# Sheet2.net
KiCad netlist of a schematic drawn in Altium Designer
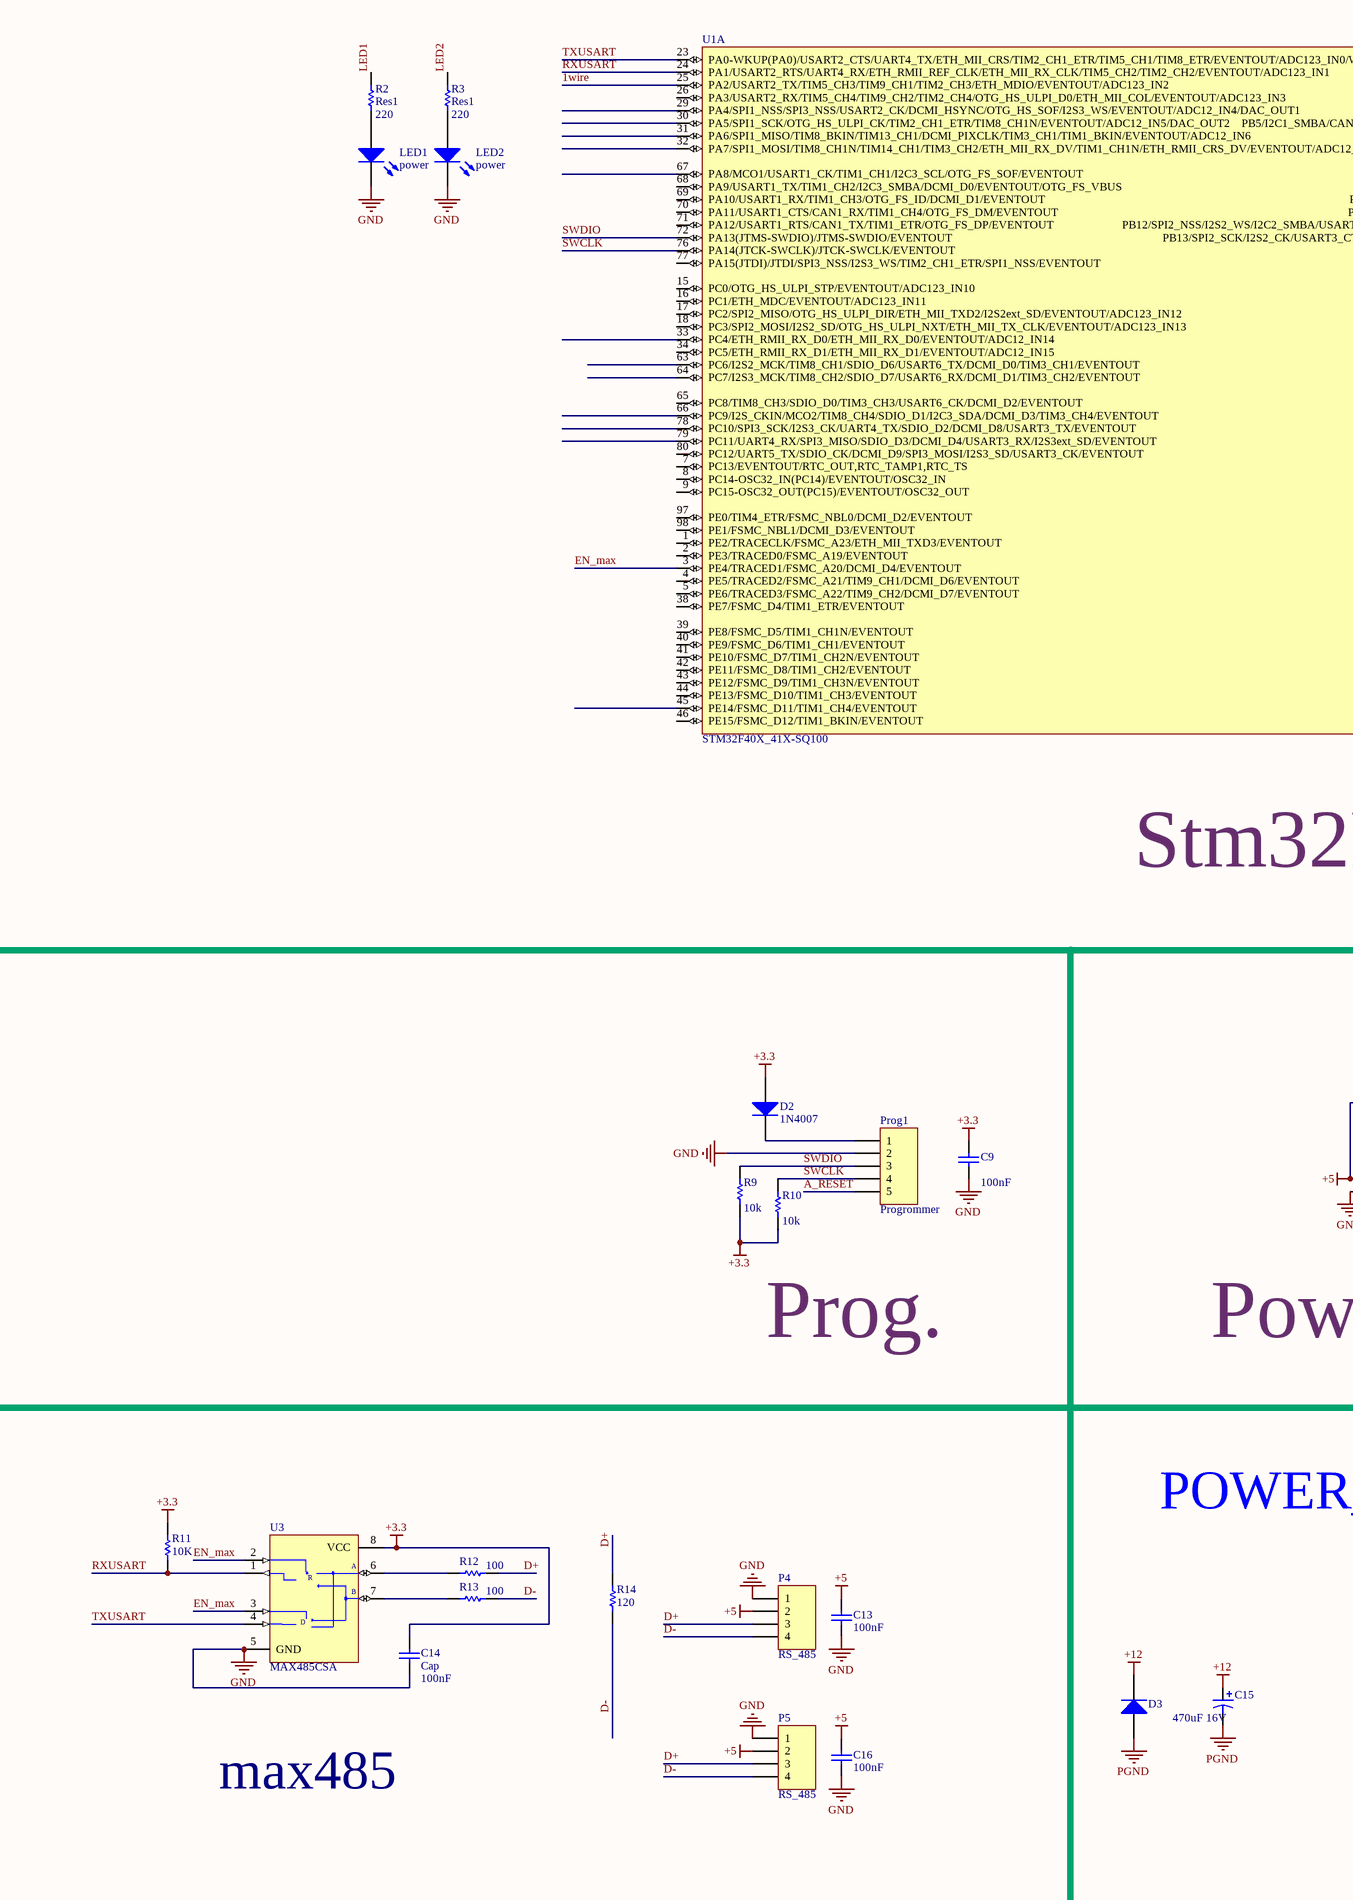
[diagram p0: Sheet2.SchDoc, left]
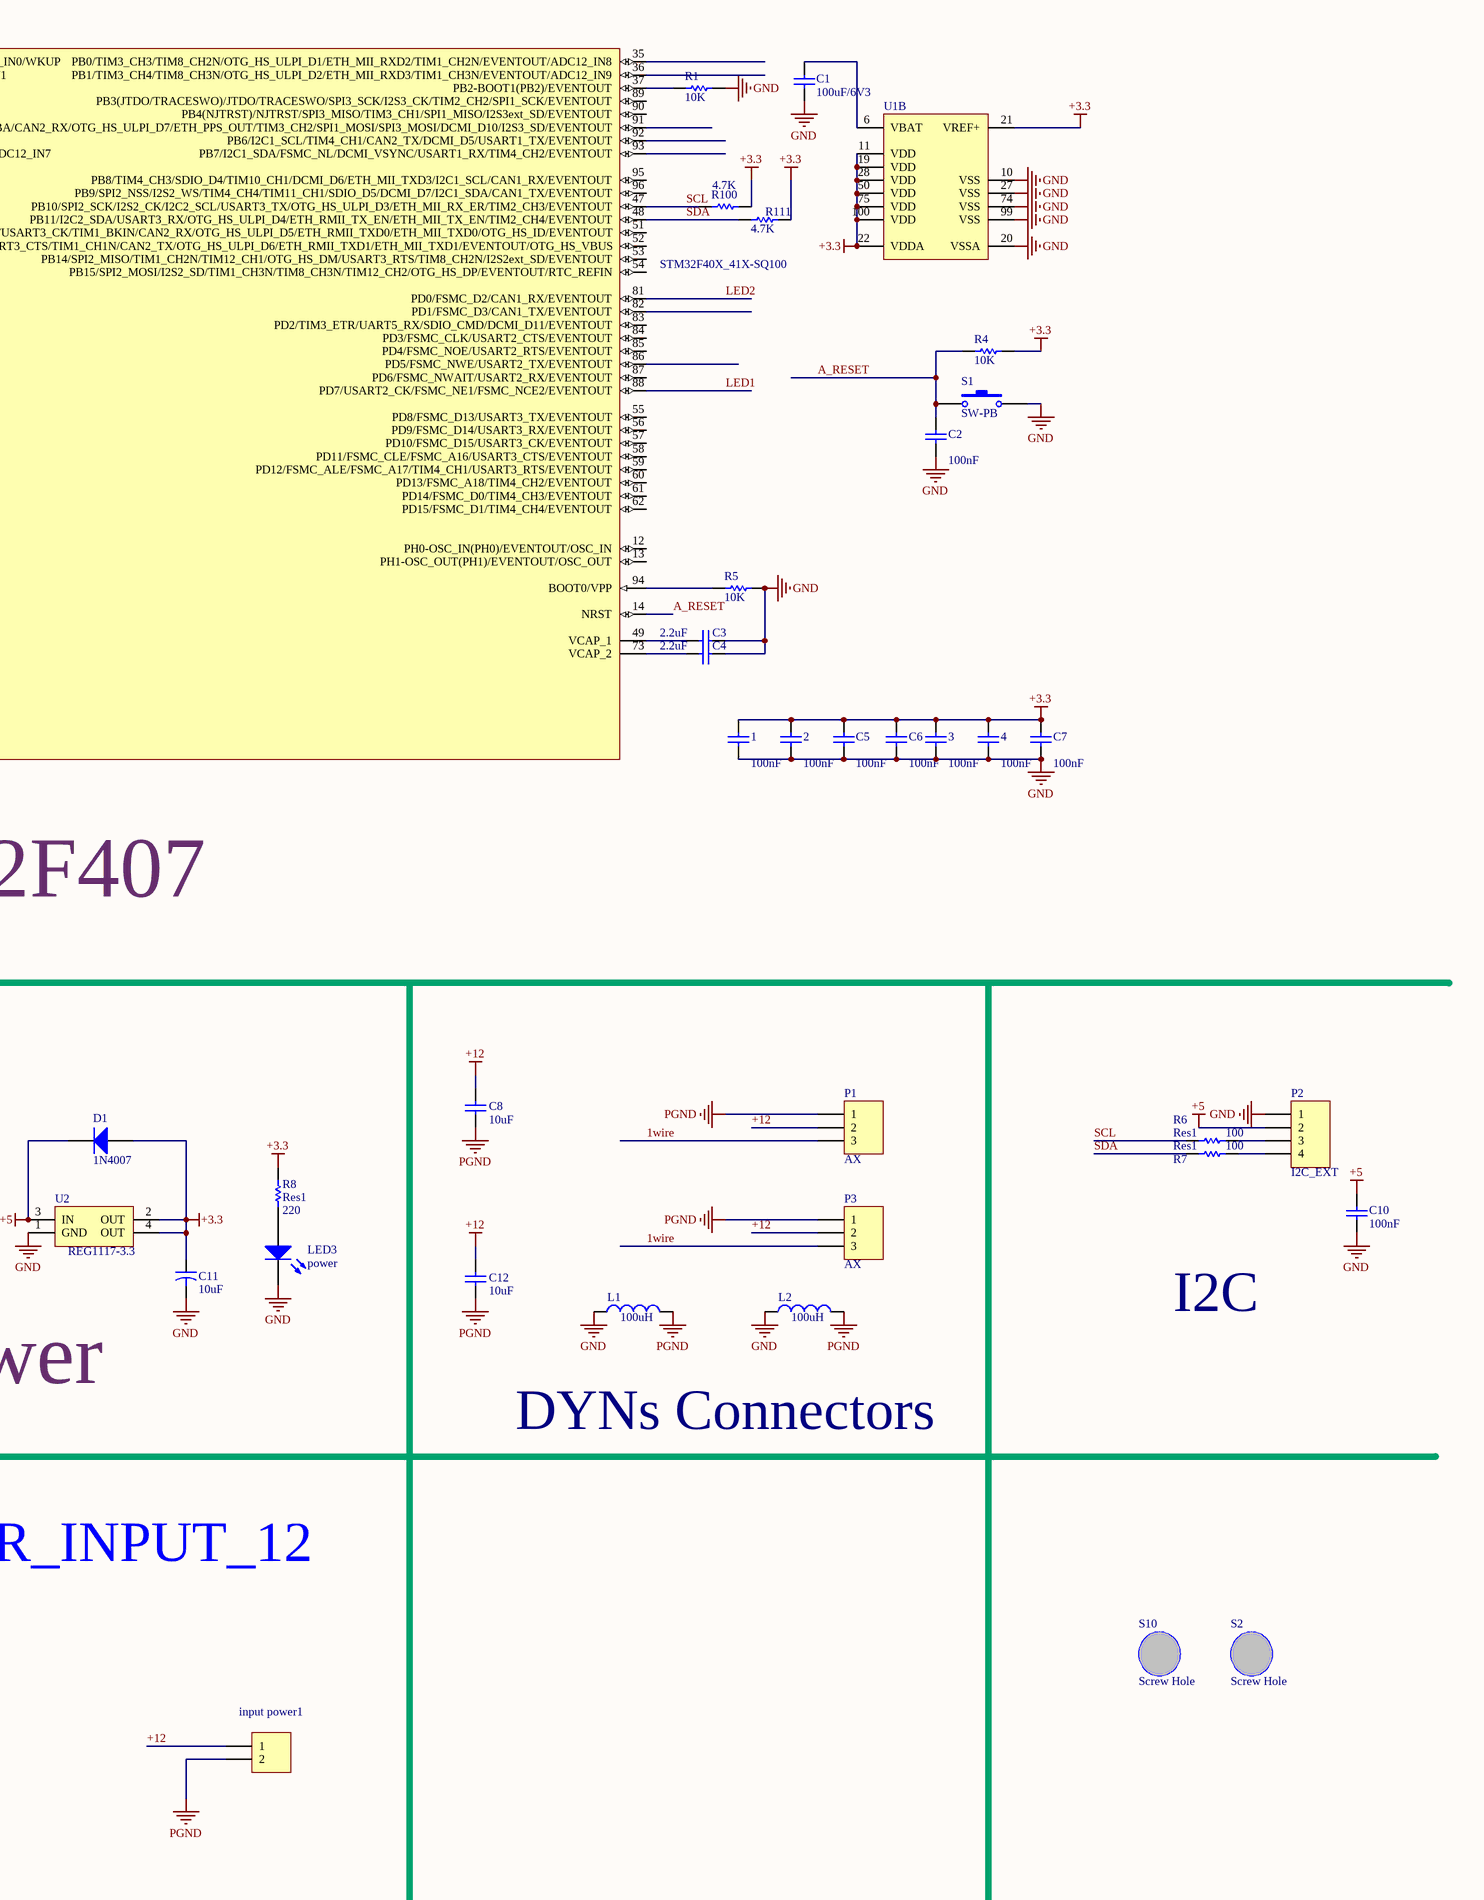
[diagram p1: Sheet2.SchDoc, right]

(export (version "E")
  (design (tool "Eeschema 10.0.6"))
  (components
    (comp (ref "1")
      (value "100nF")
      (footprint "1608[0603]")
      (description "Capacitor")
      (fields
        (field (name "MANUFACTURER") "Generic Components")
        (field (name "PUBLISHER") "Altium Hobart Technology Centre")
      )
      (libsource (lib "Miscellaneous Devices") (part "Cap"))
    )
    (comp (ref "2")
      (value "100nF")
      (footprint "1608[0603]")
      (description "Capacitor")
      (fields
        (field (name "MANUFACTURER") "Generic Components")
        (field (name "PUBLISHER") "Altium Hobart Technology Centre")
      )
      (libsource (lib "Miscellaneous Devices") (part "Cap"))
    )
    (comp (ref "3")
      (value "100nF")
      (footprint "1608[0603]")
      (description "Capacitor")
      (fields
        (field (name "MANUFACTURER") "Generic Components")
        (field (name "PUBLISHER") "Altium Hobart Technology Centre")
      )
      (libsource (lib "Miscellaneous Devices") (part "Cap"))
    )
    (comp (ref "4")
      (value "100nF")
      (footprint "1608[0603]")
      (description "Capacitor")
      (fields
        (field (name "MANUFACTURER") "Generic Components")
        (field (name "PUBLISHER") "Altium Hobart Technology Centre")
      )
      (libsource (lib "Miscellaneous Devices") (part "Cap"))
    )
    (comp (ref "C1")
      (value "100uF/6V3")
      (footprint "j1-0603")
      (description "Capacitor")
      (fields (field (name "PUBLISHER") "Altium Limited"))
      (libsource (lib "Miscellaneous Devices") (part "Cap"))
    )
    (comp (ref "C2")
      (value "100nF")
      (footprint "1608[0603]")
      (description "Capacitor")
      (fields
        (field (name "MANUFACTURER") "Generic Components")
        (field (name "PUBLISHER") "Altium Hobart Technology Centre")
      )
      (libsource (lib "Miscellaneous Devices") (part "Cap"))
    )
    (comp (ref "C3")
      (value "2.2uF")
      (footprint "j1-0603")
      (description "Capacitor")
      (fields (field (name "PUBLISHER") "Altium Limited"))
      (libsource (lib "KN2CLib") (part "Cap_UP"))
    )
    (comp (ref "C4")
      (value "2.2uF")
      (footprint "j1-0603")
      (description "Capacitor")
      (fields (field (name "PUBLISHER") "Altium Limited"))
      (libsource (lib "KN2CLib") (part "Cap_UP"))
    )
    (comp (ref "C5")
      (value "100nF")
      (footprint "1608[0603]")
      (description "Capacitor")
      (fields
        (field (name "MANUFACTURER") "Generic Components")
        (field (name "PUBLISHER") "Altium Hobart Technology Centre")
      )
      (libsource (lib "Miscellaneous Devices") (part "Cap"))
    )
    (comp (ref "C6")
      (value "100nF")
      (footprint "1608[0603]")
      (description "Capacitor")
      (fields
        (field (name "MANUFACTURER") "Generic Components")
        (field (name "PUBLISHER") "Altium Hobart Technology Centre")
      )
      (libsource (lib "Miscellaneous Devices") (part "Cap"))
    )
    (comp (ref "C7")
      (value "100nF")
      (footprint "1608[0603]")
      (description "Capacitor")
      (fields
        (field (name "MANUFACTURER") "Generic Components")
        (field (name "PUBLISHER") "Altium Hobart Technology Centre")
      )
      (libsource (lib "Miscellaneous Devices") (part "Cap"))
    )
    (comp (ref "C8")
      (value "10uF")
      (footprint "2012[0805]")
      (description "Capacitor")
      (fields (field (name "Comment") "Cap") (field (name "PUBLISHER") "Altium Limited"))
      (libsource (lib "Miscellaneous Devices") (part "Cap"))
    )
    (comp (ref "C9")
      (value "100nF")
      (footprint "1608[0603]")
      (description "Capacitor")
      (fields
        (field (name "MANUFACTURER") "Generic Components")
        (field (name "PUBLISHER") "Altium Hobart Technology Centre")
      )
      (libsource (lib "Miscellaneous Devices") (part "Cap"))
    )
    (comp (ref "C10")
      (value "100nF")
      (footprint "J1-0603")
      (description "Capacitor")
      (fields (field (name "PUBLISHER") "Altium Limited"))
      (libsource (lib "Miscellaneous Devices") (part "Cap"))
    )
    (comp (ref "C11")
      (value "10uF")
      (footprint "0805")
      (description "Capacitor")
      (fields (field (name "Comment") "Cap_El") (field (name "PUBLISHER") "Altium Limited"))
      (libsource (lib "KN2CLib") (part "Cap_El"))
    )
    (comp (ref "C12")
      (value "10uF")
      (footprint "2012[0805]")
      (description "Capacitor")
      (fields (field (name "Comment") "Cap") (field (name "PUBLISHER") "Altium Limited"))
      (libsource (lib "Miscellaneous Devices") (part "Cap"))
    )
    (comp (ref "C13")
      (value "100nF")
      (footprint "J1-0603")
      (description "Capacitor")
      (fields (field (name "PUBLISHER") "Altium Limited"))
      (libsource (lib "Miscellaneous Devices") (part "Cap"))
    )
    (comp (ref "C14")
      (value "Cap")
      (footprint "j1-0603")
      (description "Capacitor")
      (fields (field (name "ALTIUM_VALUE") "100nF") (field (name "PUBLISHER") "Altium Limited"))
      (libsource (lib "Miscellaneous Devices") (part "Cap"))
    )
    (comp (ref "C15")
      (value "470uF 16V")
      (footprint "C")
      (description "Polarized Capacitor (Radial)")
      (fields (field (name "Comment") "Cap Pol1") (field (name "PUBLISHER") "Altium Limited"))
      (libsource (lib "Miscellaneous Devices") (part "Cap Pol1"))
    )
    (comp (ref "C16")
      (value "100nF")
      (footprint "J1-0603")
      (description "Capacitor")
      (fields (field (name "PUBLISHER") "Altium Limited"))
      (libsource (lib "Miscellaneous Devices") (part "Cap"))
    )
    (comp (ref "D1")
      (value "1N4007")
      (footprint "US1M")
      (description "1 Amp General Purpose Rectifier")
      (fields (field (name "PUBLISHER") "Altium Limited"))
      (libsource (lib "KN2CLib") (part "Diode"))
    )
    (comp (ref "D2")
      (value "1N4007")
      (footprint "US1M")
      (description "1 Amp General Purpose Rectifier")
      (fields (field (name "PUBLISHER") "Altium Limited"))
      (libsource (lib "KN2CLib") (part "Diode"))
    )
    (comp (ref "D3")
      (value "~")
      (footprint "us1m")
      (description "Default Diode")
      (fields
        (field (name "MANUFACTURER") "Generic Components")
        (field (name "PUBLISHER") "Altium Hobart Technology Centre")
      )
      (libsource (lib "Miscellaneous Devices") (part "Diode"))
    )
    (comp (ref "input power1")
      (value "Header 2")
      (footprint "CON2-TIWAN")
      (description "Header, 2-Pin")
      (fields (field (name "PUBLISHER") "Altium Limited"))
      (libsource (lib "KN2CLib") (part "Header 2"))
    )
    (comp (ref "L1")
      (value "100uH")
      (footprint "2012[0805]")
      (description "Inductor")
      (fields
        (field (name "MANUFACTURER") "Generic Components")
        (field (name "PUBLISHER") "Altium Hobart Technology Centre")
      )
      (libsource (lib "Miscellaneous Devices") (part "Inductor"))
    )
    (comp (ref "L2")
      (value "100uH")
      (footprint "2012[0805]")
      (description "Inductor")
      (fields
        (field (name "MANUFACTURER") "Generic Components")
        (field (name "PUBLISHER") "Altium Hobart Technology Centre")
      )
      (libsource (lib "Miscellaneous Devices") (part "Inductor"))
    )
    (comp (ref "LED1")
      (value "power")
      (footprint "3518")
      (description "Typical BLUE SiC LED")
      (fields (field (name "PUBLISHER") "Altium Limited"))
      (libsource (lib "Miscellaneous Devices") (part "LED3"))
    )
    (comp (ref "LED2")
      (value "power")
      (footprint "3518")
      (description "Typical BLUE SiC LED")
      (fields (field (name "PUBLISHER") "Altium Limited"))
      (libsource (lib "Miscellaneous Devices") (part "LED3"))
    )
    (comp (ref "LED3")
      (value "power")
      (footprint "3518")
      (description "Typical BLUE SiC LED")
      (fields (field (name "PUBLISHER") "Altium Limited"))
      (libsource (lib "Miscellaneous Devices") (part "LED3"))
    )
    (comp (ref "P1")
      (value "AX")
      (footprint "jp circular 3")
      (description "Header, 3-Pin")
      (fields (field (name "PUBLISHER") "Altium Limited"))
      (libsource (lib "KN2CLib") (part "jp circular 3"))
    )
    (comp (ref "P2")
      (value "I2C_EXT")
      (footprint "jp circular 4")
      (description "Header, 4-Pin")
      (fields (field (name "PUBLISHER") "Altium Limited"))
      (libsource (lib "KN2CLib") (part "jp circular 4"))
    )
    (comp (ref "P3")
      (value "AX")
      (footprint "jp circular 3")
      (description "Header, 3-Pin")
      (fields (field (name "PUBLISHER") "Altium Limited"))
      (libsource (lib "KN2CLib") (part "jp circular 3"))
    )
    (comp (ref "P4")
      (value "RS_485")
      (footprint "jp circular 4")
      (description "Header, 4-Pin")
      (fields (field (name "PUBLISHER") "Altium Limited"))
      (libsource (lib "Miscellaneous Connectors") (part "Header 4"))
    )
    (comp (ref "P5")
      (value "RS_485")
      (footprint "jp circular 4")
      (description "Header, 4-Pin")
      (fields (field (name "PUBLISHER") "Altium Limited"))
      (libsource (lib "Miscellaneous Connectors") (part "Header 4"))
    )
    (comp (ref "Prog1")
      (value "Progrommer")
      (footprint "HDR1x5")
      (description "Header, 5-Pin")
      (fields (field (name "PUBLISHER") "Altium Limited"))
      (libsource (lib "Miscellaneous Connectors") (part "Header 5"))
    )
    (comp (ref "R1")
      (value "10K")
      (footprint "J1-0603")
      (description "Resistor")
      (fields (field (name "PUBLISHER") "Altium Limited"))
      (libsource (lib "Miscellaneous Devices") (part "Res1"))
    )
    (comp (ref "R2")
      (value "Res1")
      (footprint "j1-0603")
      (description "Resistor")
      (fields (field (name "ALTIUM_VALUE") "220") (field (name "PUBLISHER") "Altium Limited"))
      (libsource (lib "Miscellaneous Devices") (part "Res1"))
    )
    (comp (ref "R3")
      (value "Res1")
      (footprint "j1-0603")
      (description "Resistor")
      (fields (field (name "ALTIUM_VALUE") "220") (field (name "PUBLISHER") "Altium Limited"))
      (libsource (lib "Miscellaneous Devices") (part "Res1"))
    )
    (comp (ref "R4")
      (value "10K")
      (footprint "J1-0603")
      (description "Resistor")
      (fields (field (name "PUBLISHER") "Altium Limited"))
      (libsource (lib "Miscellaneous Devices") (part "Res1"))
    )
    (comp (ref "R5")
      (value "10K")
      (footprint "J1-0603")
      (description "Resistor")
      (fields (field (name "PUBLISHER") "Altium Limited"))
      (libsource (lib "Miscellaneous Devices") (part "Res1"))
    )
    (comp (ref "R6")
      (value "Res1")
      (footprint "j1-0603")
      (description "Resistor")
      (fields (field (name "ALTIUM_VALUE") "100") (field (name "PUBLISHER") "Altium Limited"))
      (libsource (lib "Miscellaneous Devices") (part "Res1"))
    )
    (comp (ref "R7")
      (value "Res1")
      (footprint "j1-0603")
      (description "Resistor")
      (fields (field (name "ALTIUM_VALUE") "100") (field (name "PUBLISHER") "Altium Limited"))
      (libsource (lib "Miscellaneous Devices") (part "Res1"))
    )
    (comp (ref "R8")
      (value "Res1")
      (footprint "j1-0603")
      (description "Resistor")
      (fields (field (name "ALTIUM_VALUE") "220") (field (name "PUBLISHER") "Altium Limited"))
      (libsource (lib "Miscellaneous Devices") (part "Res1"))
    )
    (comp (ref "R9")
      (value "10k")
      (footprint "J1-0603")
      (description "Semiconductor Resistor")
      (fields (field (name "PUBLISHER") "Altium Limited"))
      (libsource (lib "KN2CLib") (part "Res"))
    )
    (comp (ref "R10")
      (value "10k")
      (footprint "J1-0603")
      (description "Semiconductor Resistor")
      (fields (field (name "PUBLISHER") "Altium Limited"))
      (libsource (lib "KN2CLib") (part "Res"))
    )
    (comp (ref "R11")
      (value "10K")
      (footprint "j1-0603")
      (description "Resistor")
      (fields (field (name "Comment") "Res1") (field (name "PUBLISHER") "Altium Limited"))
      (libsource (lib "Miscellaneous Devices") (part "Res1"))
    )
    (comp (ref "R12")
      (value "100")
      (footprint "j1-0603")
      (description "Resistor")
      (fields (field (name "Comment") "Res1") (field (name "PUBLISHER") "Altium Limited"))
      (libsource (lib "Miscellaneous Devices") (part "Res1"))
    )
    (comp (ref "R13")
      (value "100")
      (footprint "j1-0603")
      (description "Resistor")
      (fields (field (name "Comment") "Res1") (field (name "PUBLISHER") "Altium Limited"))
      (libsource (lib "Miscellaneous Devices") (part "Res1"))
    )
    (comp (ref "R14")
      (value "120")
      (footprint "j1-0603")
      (description "Resistor")
      (fields (field (name "Comment") "Res1") (field (name "PUBLISHER") "Altium Limited"))
      (libsource (lib "Miscellaneous Devices") (part "Res1"))
    )
    (comp (ref "R100")
      (value "4.7K")
      (footprint "J1-0603")
      (description "Resistor")
      (fields (field (name "PUBLISHER") "Altium Limited"))
      (libsource (lib "Miscellaneous Devices") (part "Res1"))
    )
    (comp (ref "R111")
      (value "4.7K")
      (footprint "J1-0603")
      (description "Resistor")
      (fields (field (name "PUBLISHER") "Altium Limited"))
      (libsource (lib "Miscellaneous Devices") (part "Res1"))
    )
    (comp (ref "S1")
      (value "SW-PB")
      (footprint "SW-PB-4P")
      (description "Switch")
      (fields (field (name "PUBLISHER") "Altium Limited"))
      (libsource (lib "Miscellaneous Devices") (part "SW-PB"))
    )
    (comp (ref "S2")
      (value "Screw Hole")
      (footprint "Screw Holw 3-6 mm")
      (libsource (lib "KN2CLib") (part "Screw Hole"))
    )
    (comp (ref "S10")
      (value "Screw Hole")
      (footprint "Screw Holw 3-6 mm")
      (libsource (lib "KN2CLib") (part "Screw Hole"))
    )
    (comp (ref "U1")
      (value "STM32F40X_41X-SQ100")
      (footprint "100A_N")
      (libsource (lib "KN2CLib") (part "STM32F40X_41X-SQ100"))
    )
    (comp (ref "U2")
      (value "REG1117-3.3")
      (footprint "SOT223")
      (description "800mA and 1A Low Dropout Positive Regulator 2.85V, 3.3V, 5V, and Adjustable")
      (fields (field (name "PUBLISHER") "Altium Limited"))
      (libsource (lib "BB Power Mgt Voltage Regulator") (part "REG1117-3.3"))
    )
    (comp (ref "U3")
      (value "MAX485CSA")
      (footprint "NSO8_N")
      (description "Low-Power, Slew-Rate-Limited RS-485/RS-422 Transceiver")
      (fields (field (name "PUBLISHER") "Altium Limited"))
      (libsource (lib "Maxim Communication Transceiver") (part "MAX485CSA"))
    )
  )
  (nets
    (net (code "1") (name "+3.3") (class "Default")
      (node (ref "1") (pin "2") (pinfunction "2_2") (pintype "passive"))
      (node (ref "2") (pin "2") (pinfunction "2_2") (pintype "passive"))
      (node (ref "3") (pin "2") (pinfunction "2_2") (pintype "passive"))
      (node (ref "4") (pin "2") (pinfunction "2_2") (pintype "passive"))
      (node (ref "C11") (pin "1") (pinfunction "1_1") (pintype "passive"))
      (node (ref "C14") (pin "2") (pinfunction "2_2") (pintype "passive"))
      (node (ref "C5") (pin "2") (pinfunction "2_2") (pintype "passive"))
      (node (ref "C6") (pin "2") (pinfunction "2_2") (pintype "passive"))
      (node (ref "C7") (pin "2") (pinfunction "2_2") (pintype "passive"))
      (node (ref "C9") (pin "2") (pinfunction "2_2") (pintype "passive"))
      (node (ref "D1") (pin "1") (pinfunction "A_1") (pintype "passive"))
      (node (ref "D2") (pin "1") (pinfunction "A_1") (pintype "passive"))
      (node (ref "R10") (pin "2") (pinfunction "2_2") (pintype "passive"))
      (node (ref "R100") (pin "1") (pinfunction "1_1") (pintype "passive"))
      (node (ref "R11") (pin "1") (pinfunction "1_1") (pintype "passive"))
      (node (ref "R111") (pin "1") (pinfunction "1_1") (pintype "passive"))
      (node (ref "R4") (pin "1") (pinfunction "1_1") (pintype "passive"))
      (node (ref "R8") (pin "1") (pinfunction "1_1") (pintype "passive"))
      (node (ref "R9") (pin "2") (pinfunction "2_2") (pintype "passive"))
      (node (ref "U1") (pin "100") (pinfunction "VDD_100") (pintype "power_in"))
      (node (ref "U1") (pin "11") (pinfunction "VDD_11") (pintype "power_in"))
      (node (ref "U1") (pin "19") (pinfunction "VDD_19") (pintype "power_in"))
      (node (ref "U1") (pin "21") (pinfunction "VREF+_21") (pintype "power_in"))
      (node (ref "U1") (pin "22") (pinfunction "VDDA_22") (pintype "power_in"))
      (node (ref "U1") (pin "28") (pinfunction "VDD_28") (pintype "power_in"))
      (node (ref "U1") (pin "50") (pinfunction "VDD_50") (pintype "power_in"))
      (node (ref "U1") (pin "75") (pinfunction "VDD_75") (pintype "power_in"))
      (node (ref "U2") (pin "2") (pinfunction "OUT_2") (pintype "power_in"))
      (node (ref "U2") (pin "4") (pinfunction "OUT_4") (pintype "power_in"))
      (node (ref "U3") (pin "8") (pinfunction "VCC_8") (pintype "power_in"))
    )
    (net (code "2") (name "+5") (class "Default")
      (node (ref "C10") (pin "2") (pinfunction "2_2") (pintype "passive"))
      (node (ref "C13") (pin "2") (pinfunction "2_2") (pintype "passive"))
      (node (ref "C16") (pin "2") (pinfunction "2_2") (pintype "passive"))
      (node (ref "D1") (pin "2") (pinfunction "K_2") (pintype "passive"))
      (node (ref "P2") (pin "2") (pinfunction "2_2") (pintype "passive"))
      (node (ref "P4") (pin "2") (pinfunction "2_2") (pintype "passive"))
      (node (ref "P5") (pin "2") (pinfunction "2_2") (pintype "passive"))
      (node (ref "U2") (pin "3") (pinfunction "IN_3") (pintype "power_in"))
    )
    (net (code "3") (name "+12") (class "Default")
      (node (ref "C12") (pin "2") (pinfunction "2_2") (pintype "passive"))
      (node (ref "C15") (pin "1") (pinfunction "1_1") (pintype "passive"))
      (node (ref "C8") (pin "2") (pinfunction "2_2") (pintype "passive"))
      (node (ref "D3") (pin "2") (pinfunction "K_2") (pintype "passive"))
      (node (ref "P1") (pin "2") (pinfunction "2_2") (pintype "passive"))
      (node (ref "P3") (pin "2") (pinfunction "2_2") (pintype "passive"))
      (node (ref "input power1") (pin "1") (pinfunction "1_1") (pintype "passive"))
    )
    (net (code "4") (name "/1wire") (class "Default")
      (node (ref "P1") (pin "3") (pinfunction "3_3") (pintype "passive"))
      (node (ref "P3") (pin "3") (pinfunction "3_3") (pintype "passive"))
      (node (ref "U1") (pin "25") (pinfunction "PA2/USART2_TX/TIM5_CH3/TIM9_CH1/TIM2_CH3/ETH_MDIO/EVENTOUT/ADC123_IN2_25") (pintype "bidirectional"))
    )
    (net (code "5") (name "/A_RESET") (class "Default")
      (node (ref "C2") (pin "2") (pinfunction "2_2") (pintype "passive"))
      (node (ref "Prog1") (pin "5") (pinfunction "5_5") (pintype "passive"))
      (node (ref "R4") (pin "2") (pinfunction "2_2") (pintype "passive"))
      (node (ref "S1") (pin "1") (pinfunction "1_1") (pintype "passive"))
      (node (ref "U1") (pin "14") (pinfunction "NRST_14") (pintype "bidirectional"))
    )
    (net (code "6") (name "/D+") (class "Default")
      (node (ref "P4") (pin "3") (pinfunction "3_3") (pintype "passive"))
      (node (ref "P5") (pin "3") (pinfunction "3_3") (pintype "passive"))
      (node (ref "R12") (pin "2") (pinfunction "2_2") (pintype "passive"))
      (node (ref "R14") (pin "1") (pinfunction "1_1") (pintype "passive"))
    )
    (net (code "7") (name "/D-") (class "Default")
      (node (ref "P4") (pin "4") (pinfunction "4_4") (pintype "passive"))
      (node (ref "P5") (pin "4") (pinfunction "4_4") (pintype "passive"))
      (node (ref "R13") (pin "2") (pinfunction "2_2") (pintype "passive"))
      (node (ref "R14") (pin "2") (pinfunction "2_2") (pintype "passive"))
    )
    (net (code "8") (name "/EN_max") (class "Default")
      (node (ref "U1") (pin "3") (pinfunction "PE4/TRACED1/FSMC_A20/DCMI_D4/EVENTOUT_3") (pintype "bidirectional"))
      (node (ref "U3") (pin "2") (pinfunction "~{RE}_2") (pintype "input"))
      (node (ref "U3") (pin "3") (pinfunction "DE_3") (pintype "input"))
    )
    (net (code "9") (name "/LED1") (class "Default")
      (node (ref "R2") (pin "1") (pinfunction "1_1") (pintype "passive"))
      (node (ref "U1") (pin "88") (pinfunction "PD7/USART2_CK/FSMC_NE1/FSMC_NCE2/EVENTOUT_88") (pintype "bidirectional"))
    )
    (net (code "10") (name "/LED2") (class "Default")
      (node (ref "R3") (pin "1") (pinfunction "1_1") (pintype "passive"))
      (node (ref "U1") (pin "81") (pinfunction "PD0/FSMC_D2/CAN1_RX/EVENTOUT_81") (pintype "bidirectional"))
    )
    (net (code "11") (name "/RXUSART") (class "Default")
      (node (ref "R11") (pin "2") (pinfunction "2_2") (pintype "passive"))
      (node (ref "U1") (pin "24") (pinfunction "PA1/USART2_RTS/UART4_RX/ETH_RMII_REF_CLK/ETH_MII_RX_CLK/TIM5_CH2/TIM2_CH2/EVENTOUT/ADC123_IN1_24") (pintype "bidirectional"))
      (node (ref "U3") (pin "1") (pinfunction "RO_1") (pintype "output"))
    )
    (net (code "12") (name "/SCL") (class "Default")
      (node (ref "R100") (pin "2") (pinfunction "2_2") (pintype "passive"))
      (node (ref "R6") (pin "1") (pinfunction "1_1") (pintype "passive"))
      (node (ref "U1") (pin "47") (pinfunction "PB10/SPI2_SCK/I2S2_CK/I2C2_SCL/USART3_TX/OTG_HS_ULPI_D3/ETH_MII_RX_ER/TIM2_CH3/EVENTOUT_47") (pintype "bidirectional"))
    )
    (net (code "13") (name "/SDA") (class "Default")
      (node (ref "R111") (pin "2") (pinfunction "2_2") (pintype "passive"))
      (node (ref "R7") (pin "1") (pinfunction "1_1") (pintype "passive"))
      (node (ref "U1") (pin "48") (pinfunction "PB11/I2C2_SDA/USART3_RX/OTG_HS_ULPI_D4/ETH_RMII_TX_EN/ETH_MII_TX_EN/TIM2_CH4/EVENTOUT_48") (pintype "bidirectional"))
    )
    (net (code "14") (name "/SWCLK") (class "Default")
      (node (ref "Prog1") (pin "4") (pinfunction "4_4") (pintype "passive"))
      (node (ref "R10") (pin "1") (pinfunction "1_1") (pintype "passive"))
      (node (ref "U1") (pin "76") (pinfunction "PA14(JTCK-SWCLK)/JTCK-SWCLK/EVENTOUT_76") (pintype "bidirectional"))
    )
    (net (code "15") (name "/SWDIO") (class "Default")
      (node (ref "Prog1") (pin "3") (pinfunction "3_3") (pintype "passive"))
      (node (ref "R9") (pin "1") (pinfunction "1_1") (pintype "passive"))
      (node (ref "U1") (pin "72") (pinfunction "PA13(JTMS-SWDIO)/JTMS-SWDIO/EVENTOUT_72") (pintype "bidirectional"))
    )
    (net (code "16") (name "/TXUSART") (class "Default")
      (node (ref "U1") (pin "23") (pinfunction "PA0-WKUP(PA0)/USART2_CTS/UART4_TX/ETH_MII_CRS/TIM2_CH1_ETR/TIM5_CH1/TIM8_ETR/EVENTOUT/ADC123_IN0/WKUP_23") (pintype "bidirectional"))
      (node (ref "U3") (pin "4") (pinfunction "DI_4") (pintype "input"))
    )
    (net (code "17") (name "GND") (class "Default")
      (node (ref "1") (pin "1") (pinfunction "1_1") (pintype "passive"))
      (node (ref "2") (pin "1") (pinfunction "1_1") (pintype "passive"))
      (node (ref "3") (pin "1") (pinfunction "1_1") (pintype "passive"))
      (node (ref "4") (pin "1") (pinfunction "1_1") (pintype "passive"))
      (node (ref "C1") (pin "1") (pinfunction "1_1") (pintype "passive"))
      (node (ref "C10") (pin "1") (pinfunction "1_1") (pintype "passive"))
      (node (ref "C11") (pin "2") (pinfunction "2_2") (pintype "passive"))
      (node (ref "C13") (pin "1") (pinfunction "1_1") (pintype "passive"))
      (node (ref "C14") (pin "1") (pinfunction "1_1") (pintype "passive"))
      (node (ref "C16") (pin "1") (pinfunction "1_1") (pintype "passive"))
      (node (ref "C2") (pin "1") (pinfunction "1_1") (pintype "passive"))
      (node (ref "C3") (pin "2") (pinfunction "2_2") (pintype "passive"))
      (node (ref "C4") (pin "2") (pinfunction "2_2") (pintype "passive"))
      (node (ref "C5") (pin "1") (pinfunction "1_1") (pintype "passive"))
      (node (ref "C6") (pin "1") (pinfunction "1_1") (pintype "passive"))
      (node (ref "C7") (pin "1") (pinfunction "1_1") (pintype "passive"))
      (node (ref "C9") (pin "1") (pinfunction "1_1") (pintype "passive"))
      (node (ref "L1") (pin "1") (pinfunction "1_1") (pintype "passive"))
      (node (ref "L2") (pin "1") (pinfunction "1_1") (pintype "passive"))
      (node (ref "LED1") (pin "2") (pinfunction "K_2") (pintype "passive"))
      (node (ref "LED2") (pin "2") (pinfunction "K_2") (pintype "passive"))
      (node (ref "LED3") (pin "2") (pinfunction "K_2") (pintype "passive"))
      (node (ref "P2") (pin "1") (pinfunction "1_1") (pintype "passive"))
      (node (ref "P4") (pin "1") (pinfunction "1_1") (pintype "passive"))
      (node (ref "P5") (pin "1") (pinfunction "1_1") (pintype "passive"))
      (node (ref "Prog1") (pin "2") (pinfunction "2_2") (pintype "passive"))
      (node (ref "R1") (pin "1") (pinfunction "1_1") (pintype "passive"))
      (node (ref "R5") (pin "1") (pinfunction "1_1") (pintype "passive"))
      (node (ref "S1") (pin "2") (pinfunction "2_2") (pintype "passive"))
      (node (ref "U1") (pin "10") (pinfunction "VSS_10") (pintype "power_in"))
      (node (ref "U1") (pin "20") (pinfunction "VSSA_20") (pintype "power_in"))
      (node (ref "U1") (pin "27") (pinfunction "VSS_27") (pintype "power_in"))
      (node (ref "U1") (pin "74") (pinfunction "VSS_74") (pintype "power_in"))
      (node (ref "U1") (pin "99") (pinfunction "VSS_99") (pintype "power_in"))
      (node (ref "U2") (pin "1") (pinfunction "GND_1") (pintype "power_in"))
      (node (ref "U3") (pin "5") (pinfunction "GND_5") (pintype "power_in"))
    )
    (net (code "18") (name "Net-(D2-K)") (class "Default")
      (node (ref "D2") (pin "2") (pinfunction "K_2") (pintype "passive"))
      (node (ref "Prog1") (pin "1") (pinfunction "1_1") (pintype "passive"))
    )
    (net (code "19") (name "Net-(LED1-A)") (class "Default")
      (node (ref "LED1") (pin "1") (pinfunction "A_1") (pintype "passive"))
      (node (ref "R2") (pin "2") (pinfunction "2_2") (pintype "passive"))
    )
    (net (code "20") (name "Net-(LED2-A)") (class "Default")
      (node (ref "LED2") (pin "1") (pinfunction "A_1") (pintype "passive"))
      (node (ref "R3") (pin "2") (pinfunction "2_2") (pintype "passive"))
    )
    (net (code "21") (name "Net-(LED3-A)") (class "Default")
      (node (ref "LED3") (pin "1") (pinfunction "A_1") (pintype "passive"))
      (node (ref "R8") (pin "2") (pinfunction "2_2") (pintype "passive"))
    )
    (net (code "22") (name "Net-(P2-Pad3)") (class "Default")
      (node (ref "P2") (pin "3") (pinfunction "3_3") (pintype "passive"))
      (node (ref "R6") (pin "2") (pinfunction "2_2") (pintype "passive"))
    )
    (net (code "23") (name "Net-(P2-Pad4)") (class "Default")
      (node (ref "P2") (pin "4") (pinfunction "4_4") (pintype "passive"))
      (node (ref "R7") (pin "2") (pinfunction "2_2") (pintype "passive"))
    )
    (net (code "24") (name "Net-(U1A-BOOT0{slash}VPP)") (class "Default")
      (node (ref "R5") (pin "2") (pinfunction "2_2") (pintype "passive"))
      (node (ref "U1") (pin "94") (pinfunction "BOOT0/VPP_94") (pintype "input"))
    )
    (net (code "25") (name "Net-(U1A-PB2-BOOT1(PB2){slash}EVENTOUT)") (class "Default")
      (node (ref "R1") (pin "2") (pinfunction "2_2") (pintype "passive"))
      (node (ref "U1") (pin "37") (pinfunction "PB2-BOOT1(PB2)/EVENTOUT_37") (pintype "bidirectional"))
    )
    (net (code "26") (name "Net-(U1A-VCAP_1)") (class "Default")
      (node (ref "C3") (pin "1") (pinfunction "1_1") (pintype "passive"))
      (node (ref "U1") (pin "49") (pinfunction "VCAP_1_49") (pintype "power_in"))
    )
    (net (code "27") (name "Net-(U1A-VCAP_2)") (class "Default")
      (node (ref "C4") (pin "1") (pinfunction "1_1") (pintype "passive"))
      (node (ref "U1") (pin "73") (pinfunction "VCAP_2_73") (pintype "power_in"))
    )
    (net (code "28") (name "Net-(U1B-VBAT)") (class "Default")
      (node (ref "C1") (pin "2") (pinfunction "2_2") (pintype "passive"))
      (node (ref "U1") (pin "6") (pinfunction "VBAT_6") (pintype "power_in"))
    )
    (net (code "29") (name "Net-(U3-A)") (class "Default")
      (node (ref "R12") (pin "1") (pinfunction "1_1") (pintype "passive"))
      (node (ref "U3") (pin "6") (pinfunction "A_6") (pintype "bidirectional"))
    )
    (net (code "30") (name "Net-(U3-B)") (class "Default")
      (node (ref "R13") (pin "1") (pinfunction "1_1") (pintype "passive"))
      (node (ref "U3") (pin "7") (pinfunction "B_7") (pintype "bidirectional"))
    )
    (net (code "31") (name "PGND") (class "Default")
      (node (ref "C12") (pin "1") (pinfunction "1_1") (pintype "passive"))
      (node (ref "C15") (pin "2") (pinfunction "2_2") (pintype "passive"))
      (node (ref "C8") (pin "1") (pinfunction "1_1") (pintype "passive"))
      (node (ref "D3") (pin "1") (pinfunction "A_1") (pintype "passive"))
      (node (ref "L1") (pin "2") (pinfunction "2_2") (pintype "passive"))
      (node (ref "L2") (pin "2") (pinfunction "2_2") (pintype "passive"))
      (node (ref "P1") (pin "1") (pinfunction "1_1") (pintype "passive"))
      (node (ref "P3") (pin "1") (pinfunction "1_1") (pintype "passive"))
      (node (ref "input power1") (pin "2") (pinfunction "2_2") (pintype "passive"))
    )
    (net (code "32") (name "unconnected-(U1A-PA3{slash}USART2_RX{slash}TIM5_CH4{slash}TIM9_CH2{slash}TIM2_CH4{slash}OTG_HS_ULPI_D0{slash}ETH_MII_COL{slash}EVENTOUT{slash}ADC123_IN3-Pad26)") (class "Default")
      (node (ref "U1") (pin "26") (pinfunction "PA3/USART2_RX/TIM5_CH4/TIM9_CH2/TIM2_CH4/OTG_HS_ULPI_D0/ETH_MII_COL/EVENTOUT/ADC123_IN3_26") (pintype "bidirectional"))
    )
    (net (code "33") (name "unconnected-(U1A-PA4{slash}SPI1_NSS{slash}SPI3_NSS{slash}USART2_CK{slash}DCMI_HSYNC{slash}OTG_HS_SOF{slash}I2S3_WS{slash}EVENTOUT{slash}ADC12_IN4{slash}DAC_OUT1-Pad29)") (class "Default")
      (node (ref "U1") (pin "29") (pinfunction "PA4/SPI1_NSS/SPI3_NSS/USART2_CK/DCMI_HSYNC/OTG_HS_SOF/I2S3_WS/EVENTOUT/ADC12_IN4/DAC_OUT1_29") (pintype "bidirectional"))
    )
    (net (code "34") (name "unconnected-(U1A-PA5{slash}SPI1_SCK{slash}OTG_HS_ULPI_CK{slash}TIM2_CH1_ETR{slash}TIM8_CH1N{slash}EVENTOUT{slash}ADC12_IN5{slash}DAC_OUT2-Pad30)") (class "Default")
      (node (ref "U1") (pin "30") (pinfunction "PA5/SPI1_SCK/OTG_HS_ULPI_CK/TIM2_CH1_ETR/TIM8_CH1N/EVENTOUT/ADC12_IN5/DAC_OUT2_30") (pintype "bidirectional"))
    )
    (net (code "35") (name "unconnected-(U1A-PA6{slash}SPI1_MISO{slash}TIM8_BKIN{slash}TIM13_CH1{slash}DCMI_PIXCLK{slash}TIM3_CH1{slash}TIM1_BKIN{slash}EVENTOUT{slash}ADC12_IN6-Pad31)") (class "Default")
      (node (ref "U1") (pin "31") (pinfunction "PA6/SPI1_MISO/TIM8_BKIN/TIM13_CH1/DCMI_PIXCLK/TIM3_CH1/TIM1_BKIN/EVENTOUT/ADC12_IN6_31") (pintype "bidirectional"))
    )
    (net (code "36") (name "unconnected-(U1A-PA7{slash}SPI1_MOSI{slash}TIM8_CH1N{slash}TIM14_CH1{slash}TIM3_CH2{slash}ETH_MII_RX_DV{slash}TIM1_CH1N{slash}ETH_RMII_CRS_DV{slash}EVENTOUT{slash}ADC12_IN7-Pad32)") (class "Default")
      (node (ref "U1") (pin "32") (pinfunction "PA7/SPI1_MOSI/TIM8_CH1N/TIM14_CH1/TIM3_CH2/ETH_MII_RX_DV/TIM1_CH1N/ETH_RMII_CRS_DV/EVENTOUT/ADC12_IN7_32") (pintype "bidirectional"))
    )
    (net (code "37") (name "unconnected-(U1A-PA8{slash}MCO1{slash}USART1_CK{slash}TIM1_CH1{slash}I2C3_SCL{slash}OTG_FS_SOF{slash}EVENTOUT-Pad67)") (class "Default")
      (node (ref "U1") (pin "67") (pinfunction "PA8/MCO1/USART1_CK/TIM1_CH1/I2C3_SCL/OTG_FS_SOF/EVENTOUT_67") (pintype "bidirectional"))
    )
    (net (code "38") (name "unconnected-(U1A-PA9{slash}USART1_TX{slash}TIM1_CH2{slash}I2C3_SMBA{slash}DCMI_D0{slash}EVENTOUT{slash}OTG_FS_VBUS-Pad68)") (class "Default")
      (node (ref "U1") (pin "68") (pinfunction "PA9/USART1_TX/TIM1_CH2/I2C3_SMBA/DCMI_D0/EVENTOUT/OTG_FS_VBUS_68") (pintype "bidirectional"))
    )
    (net (code "39") (name "unconnected-(U1A-PA10{slash}USART1_RX{slash}TIM1_CH3{slash}OTG_FS_ID{slash}DCMI_D1{slash}EVENTOUT-Pad69)") (class "Default")
      (node (ref "U1") (pin "69") (pinfunction "PA10/USART1_RX/TIM1_CH3/OTG_FS_ID/DCMI_D1/EVENTOUT_69") (pintype "bidirectional"))
    )
    (net (code "40") (name "unconnected-(U1A-PA11{slash}USART1_CTS{slash}CAN1_RX{slash}TIM1_CH4{slash}OTG_FS_DM{slash}EVENTOUT-Pad70)") (class "Default")
      (node (ref "U1") (pin "70") (pinfunction "PA11/USART1_CTS/CAN1_RX/TIM1_CH4/OTG_FS_DM/EVENTOUT_70") (pintype "bidirectional"))
    )
    (net (code "41") (name "unconnected-(U1A-PA12{slash}USART1_RTS{slash}CAN1_TX{slash}TIM1_ETR{slash}OTG_FS_DP{slash}EVENTOUT-Pad71)") (class "Default")
      (node (ref "U1") (pin "71") (pinfunction "PA12/USART1_RTS/CAN1_TX/TIM1_ETR/OTG_FS_DP/EVENTOUT_71") (pintype "bidirectional"))
    )
    (net (code "42") (name "unconnected-(U1A-PA15(JTDI){slash}JTDI{slash}SPI3_NSS{slash}I2S3_WS{slash}TIM2_CH1_ETR{slash}SPI1_NSS{slash}EVENTOUT-Pad77)") (class "Default")
      (node (ref "U1") (pin "77") (pinfunction "PA15(JTDI)/JTDI/SPI3_NSS/I2S3_WS/TIM2_CH1_ETR/SPI1_NSS/EVENTOUT_77") (pintype "bidirectional"))
    )
    (net (code "43") (name "unconnected-(U1A-PB0{slash}TIM3_CH3{slash}TIM8_CH2N{slash}OTG_HS_ULPI_D1{slash}ETH_MII_RXD2{slash}TIM1_CH2N{slash}EVENTOUT{slash}ADC12_IN8-Pad35)") (class "Default")
      (node (ref "U1") (pin "35") (pinfunction "PB0/TIM3_CH3/TIM8_CH2N/OTG_HS_ULPI_D1/ETH_MII_RXD2/TIM1_CH2N/EVENTOUT/ADC12_IN8_35") (pintype "bidirectional"))
    )
    (net (code "44") (name "unconnected-(U1A-PB1{slash}TIM3_CH4{slash}TIM8_CH3N{slash}OTG_HS_ULPI_D2{slash}ETH_MII_RXD3{slash}TIM1_CH3N{slash}EVENTOUT{slash}ADC12_IN9-Pad36)") (class "Default")
      (node (ref "U1") (pin "36") (pinfunction "PB1/TIM3_CH4/TIM8_CH3N/OTG_HS_ULPI_D2/ETH_MII_RXD3/TIM1_CH3N/EVENTOUT/ADC12_IN9_36") (pintype "bidirectional"))
    )
    (net (code "45") (name "unconnected-(U1A-PB3(JTDO{slash}TRACESWO){slash}JTDO{slash}TRACESWO{slash}SPI3_SCK{slash}I2S3_CK{slash}TIM2_CH2{slash}SPI1_SCK{slash}EVENTOUT-Pad89)") (class "Default")
      (node (ref "U1") (pin "89") (pinfunction "PB3(JTDO/TRACESWO)/JTDO/TRACESWO/SPI3_SCK/I2S3_CK/TIM2_CH2/SPI1_SCK/EVENTOUT_89") (pintype "bidirectional"))
    )
    (net (code "46") (name "unconnected-(U1A-PB4(NJTRST){slash}NJTRST{slash}SPI3_MISO{slash}TIM3_CH1{slash}SPI1_MISO{slash}I2S3ext_SD{slash}EVENTOUT-Pad90)") (class "Default")
      (node (ref "U1") (pin "90") (pinfunction "PB4(NJTRST)/NJTRST/SPI3_MISO/TIM3_CH1/SPI1_MISO/I2S3ext_SD/EVENTOUT_90") (pintype "bidirectional"))
    )
    (net (code "47") (name "unconnected-(U1A-PB5{slash}I2C1_SMBA{slash}CAN2_RX{slash}OTG_HS_ULPI_D7{slash}ETH_PPS_OUT{slash}TIM3_CH2{slash}SPI1_MOSI{slash}SPI3_MOSI{slash}DCMI_D10{slash}I2S3_SD{slash}EVENTOUT-Pad91)") (class "Default")
      (node (ref "U1") (pin "91") (pinfunction "PB5/I2C1_SMBA/CAN2_RX/OTG_HS_ULPI_D7/ETH_PPS_OUT/TIM3_CH2/SPI1_MOSI/SPI3_MOSI/DCMI_D10/I2S3_SD/EVENTOUT_91") (pintype "bidirectional"))
    )
    (net (code "48") (name "unconnected-(U1A-PB6{slash}I2C1_SCL{slash}TIM4_CH1{slash}CAN2_TX{slash}DCMI_D5{slash}USART1_TX{slash}EVENTOUT-Pad92)") (class "Default")
      (node (ref "U1") (pin "92") (pinfunction "PB6/I2C1_SCL/TIM4_CH1/CAN2_TX/DCMI_D5/USART1_TX/EVENTOUT_92") (pintype "bidirectional"))
    )
    (net (code "49") (name "unconnected-(U1A-PB7{slash}I2C1_SDA{slash}FSMC_NL{slash}DCMI_VSYNC{slash}USART1_RX{slash}TIM4_CH2{slash}EVENTOUT-Pad93)") (class "Default")
      (node (ref "U1") (pin "93") (pinfunction "PB7/I2C1_SDA/FSMC_NL/DCMI_VSYNC/USART1_RX/TIM4_CH2/EVENTOUT_93") (pintype "bidirectional"))
    )
    (net (code "50") (name "unconnected-(U1A-PB8{slash}TIM4_CH3{slash}SDIO_D4{slash}TIM10_CH1{slash}DCMI_D6{slash}ETH_MII_TXD3{slash}I2C1_SCL{slash}CAN1_RX{slash}EVENTOUT-Pad95)") (class "Default")
      (node (ref "U1") (pin "95") (pinfunction "PB8/TIM4_CH3/SDIO_D4/TIM10_CH1/DCMI_D6/ETH_MII_TXD3/I2C1_SCL/CAN1_RX/EVENTOUT_95") (pintype "bidirectional"))
    )
    (net (code "51") (name "unconnected-(U1A-PB9{slash}SPI2_NSS{slash}I2S2_WS{slash}TIM4_CH4{slash}TIM11_CH1{slash}SDIO_D5{slash}DCMI_D7{slash}I2C1_SDA{slash}CAN1_TX{slash}EVENTOUT-Pad96)") (class "Default")
      (node (ref "U1") (pin "96") (pinfunction "PB9/SPI2_NSS/I2S2_WS/TIM4_CH4/TIM11_CH1/SDIO_D5/DCMI_D7/I2C1_SDA/CAN1_TX/EVENTOUT_96") (pintype "bidirectional"))
    )
    (net (code "52") (name "unconnected-(U1A-PB12{slash}SPI2_NSS{slash}I2S2_WS{slash}I2C2_SMBA{slash}USART3_CK{slash}TIM1_BKIN{slash}CAN2_RX{slash}OTG_HS_ULPI_D5{slash}ETH_RMII_TXD0{slash}ETH_MII_TXD0{slash}OTG_HS_ID{slash}EVENTOUT-Pad51)") (class "Default")
      (node (ref "U1") (pin "51") (pinfunction "PB12/SPI2_NSS/I2S2_WS/I2C2_SMBA/USART3_CK/TIM1_BKIN/CAN2_RX/OTG_HS_ULPI_D5/ETH_RMII_TXD0/ETH_MII_TXD0/OTG_HS_ID/EVENTOUT_51") (pintype "bidirectional"))
    )
    (net (code "53") (name "unconnected-(U1A-PB13{slash}SPI2_SCK{slash}I2S2_CK{slash}USART3_CTS{slash}TIM1_CH1N{slash}CAN2_TX{slash}OTG_HS_ULPI_D6{slash}ETH_RMII_TXD1{slash}ETH_MII_TXD1{slash}EVENTOUT{slash}OTG_HS_VBUS-Pad52)") (class "Default")
      (node (ref "U1") (pin "52") (pinfunction "PB13/SPI2_SCK/I2S2_CK/USART3_CTS/TIM1_CH1N/CAN2_TX/OTG_HS_ULPI_D6/ETH_RMII_TXD1/ETH_MII_TXD1/EVENTOUT/OTG_HS_VBUS_52") (pintype "bidirectional"))
    )
    (net (code "54") (name "unconnected-(U1A-PB14{slash}SPI2_MISO{slash}TIM1_CH2N{slash}TIM12_CH1{slash}OTG_HS_DM{slash}USART3_RTS{slash}TIM8_CH2N{slash}I2S2ext_SD{slash}EVENTOUT-Pad53)") (class "Default")
      (node (ref "U1") (pin "53") (pinfunction "PB14/SPI2_MISO/TIM1_CH2N/TIM12_CH1/OTG_HS_DM/USART3_RTS/TIM8_CH2N/I2S2ext_SD/EVENTOUT_53") (pintype "bidirectional"))
    )
    (net (code "55") (name "unconnected-(U1A-PB15{slash}SPI2_MOSI{slash}I2S2_SD{slash}TIM1_CH3N{slash}TIM8_CH3N{slash}TIM12_CH2{slash}OTG_HS_DP{slash}EVENTOUT{slash}RTC_REFIN-Pad54)") (class "Default")
      (node (ref "U1") (pin "54") (pinfunction "PB15/SPI2_MOSI/I2S2_SD/TIM1_CH3N/TIM8_CH3N/TIM12_CH2/OTG_HS_DP/EVENTOUT/RTC_REFIN_54") (pintype "bidirectional"))
    )
    (net (code "56") (name "unconnected-(U1A-PC0{slash}OTG_HS_ULPI_STP{slash}EVENTOUT{slash}ADC123_IN10-Pad15)") (class "Default")
      (node (ref "U1") (pin "15") (pinfunction "PC0/OTG_HS_ULPI_STP/EVENTOUT/ADC123_IN10_15") (pintype "bidirectional"))
    )
    (net (code "57") (name "unconnected-(U1A-PC1{slash}ETH_MDC{slash}EVENTOUT{slash}ADC123_IN11-Pad16)") (class "Default")
      (node (ref "U1") (pin "16") (pinfunction "PC1/ETH_MDC/EVENTOUT/ADC123_IN11_16") (pintype "bidirectional"))
    )
    (net (code "58") (name "unconnected-(U1A-PC2{slash}SPI2_MISO{slash}OTG_HS_ULPI_DIR{slash}ETH_MII_TXD2{slash}I2S2ext_SD{slash}EVENTOUT{slash}ADC123_IN12-Pad17)") (class "Default")
      (node (ref "U1") (pin "17") (pinfunction "PC2/SPI2_MISO/OTG_HS_ULPI_DIR/ETH_MII_TXD2/I2S2ext_SD/EVENTOUT/ADC123_IN12_17") (pintype "bidirectional"))
    )
    (net (code "59") (name "unconnected-(U1A-PC3{slash}SPI2_MOSI{slash}I2S2_SD{slash}OTG_HS_ULPI_NXT{slash}ETH_MII_TX_CLK{slash}EVENTOUT{slash}ADC123_IN13-Pad18)") (class "Default")
      (node (ref "U1") (pin "18") (pinfunction "PC3/SPI2_MOSI/I2S2_SD/OTG_HS_ULPI_NXT/ETH_MII_TX_CLK/EVENTOUT/ADC123_IN13_18") (pintype "bidirectional"))
    )
    (net (code "60") (name "unconnected-(U1A-PC4{slash}ETH_RMII_RX_D0{slash}ETH_MII_RX_D0{slash}EVENTOUT{slash}ADC12_IN14-Pad33)") (class "Default")
      (node (ref "U1") (pin "33") (pinfunction "PC4/ETH_RMII_RX_D0/ETH_MII_RX_D0/EVENTOUT/ADC12_IN14_33") (pintype "bidirectional"))
    )
    (net (code "61") (name "unconnected-(U1A-PC5{slash}ETH_RMII_RX_D1{slash}ETH_MII_RX_D1{slash}EVENTOUT{slash}ADC12_IN15-Pad34)") (class "Default")
      (node (ref "U1") (pin "34") (pinfunction "PC5/ETH_RMII_RX_D1/ETH_MII_RX_D1/EVENTOUT/ADC12_IN15_34") (pintype "bidirectional"))
    )
    (net (code "62") (name "unconnected-(U1A-PC6{slash}I2S2_MCK{slash}TIM8_CH1{slash}SDIO_D6{slash}USART6_TX{slash}DCMI_D0{slash}TIM3_CH1{slash}EVENTOUT-Pad63)") (class "Default")
      (node (ref "U1") (pin "63") (pinfunction "PC6/I2S2_MCK/TIM8_CH1/SDIO_D6/USART6_TX/DCMI_D0/TIM3_CH1/EVENTOUT_63") (pintype "bidirectional"))
    )
    (net (code "63") (name "unconnected-(U1A-PC7{slash}I2S3_MCK{slash}TIM8_CH2{slash}SDIO_D7{slash}USART6_RX{slash}DCMI_D1{slash}TIM3_CH2{slash}EVENTOUT-Pad64)") (class "Default")
      (node (ref "U1") (pin "64") (pinfunction "PC7/I2S3_MCK/TIM8_CH2/SDIO_D7/USART6_RX/DCMI_D1/TIM3_CH2/EVENTOUT_64") (pintype "bidirectional"))
    )
    (net (code "64") (name "unconnected-(U1A-PC8{slash}TIM8_CH3{slash}SDIO_D0{slash}TIM3_CH3{slash}USART6_CK{slash}DCMI_D2{slash}EVENTOUT-Pad65)") (class "Default")
      (node (ref "U1") (pin "65") (pinfunction "PC8/TIM8_CH3/SDIO_D0/TIM3_CH3/USART6_CK/DCMI_D2/EVENTOUT_65") (pintype "bidirectional"))
    )
    (net (code "65") (name "unconnected-(U1A-PC9{slash}I2S_CKIN{slash}MCO2{slash}TIM8_CH4{slash}SDIO_D1{slash}I2C3_SDA{slash}DCMI_D3{slash}TIM3_CH4{slash}EVENTOUT-Pad66)") (class "Default")
      (node (ref "U1") (pin "66") (pinfunction "PC9/I2S_CKIN/MCO2/TIM8_CH4/SDIO_D1/I2C3_SDA/DCMI_D3/TIM3_CH4/EVENTOUT_66") (pintype "bidirectional"))
    )
    (net (code "66") (name "unconnected-(U1A-PC10{slash}SPI3_SCK{slash}I2S3_CK{slash}UART4_TX{slash}SDIO_D2{slash}DCMI_D8{slash}USART3_TX{slash}EVENTOUT-Pad78)") (class "Default")
      (node (ref "U1") (pin "78") (pinfunction "PC10/SPI3_SCK/I2S3_CK/UART4_TX/SDIO_D2/DCMI_D8/USART3_TX/EVENTOUT_78") (pintype "bidirectional"))
    )
    (net (code "67") (name "unconnected-(U1A-PC11{slash}UART4_RX{slash}SPI3_MISO{slash}SDIO_D3{slash}DCMI_D4{slash}USART3_RX{slash}I2S3ext_SD{slash}EVENTOUT-Pad79)") (class "Default")
      (node (ref "U1") (pin "79") (pinfunction "PC11/UART4_RX/SPI3_MISO/SDIO_D3/DCMI_D4/USART3_RX/I2S3ext_SD/EVENTOUT_79") (pintype "bidirectional"))
    )
    (net (code "68") (name "unconnected-(U1A-PC12{slash}UART5_TX{slash}SDIO_CK{slash}DCMI_D9{slash}SPI3_MOSI{slash}I2S3_SD{slash}USART3_CK{slash}EVENTOUT-Pad80)") (class "Default")
      (node (ref "U1") (pin "80") (pinfunction "PC12/UART5_TX/SDIO_CK/DCMI_D9/SPI3_MOSI/I2S3_SD/USART3_CK/EVENTOUT_80") (pintype "bidirectional"))
    )
    (net (code "69") (name "unconnected-(U1A-PC13{slash}EVENTOUT{slash}RTC_OUT,RTC_TAMP1,RTC_TS-Pad7)") (class "Default")
      (node (ref "U1") (pin "7") (pinfunction "PC13/EVENTOUT/RTC_OUT,RTC_TAMP1,RTC_TS_7") (pintype "bidirectional"))
    )
    (net (code "70") (name "unconnected-(U1A-PC14-OSC32_IN(PC14){slash}EVENTOUT{slash}OSC32_IN-Pad8)") (class "Default")
      (node (ref "U1") (pin "8") (pinfunction "PC14-OSC32_IN(PC14)/EVENTOUT/OSC32_IN_8") (pintype "bidirectional"))
    )
    (net (code "71") (name "unconnected-(U1A-PC15-OSC32_OUT(PC15){slash}EVENTOUT{slash}OSC32_OUT-Pad9)") (class "Default")
      (node (ref "U1") (pin "9") (pinfunction "PC15-OSC32_OUT(PC15)/EVENTOUT/OSC32_OUT_9") (pintype "bidirectional"))
    )
    (net (code "72") (name "unconnected-(U1A-PD1{slash}FSMC_D3{slash}CAN1_TX{slash}EVENTOUT-Pad82)") (class "Default")
      (node (ref "U1") (pin "82") (pinfunction "PD1/FSMC_D3/CAN1_TX/EVENTOUT_82") (pintype "bidirectional"))
    )
    (net (code "73") (name "unconnected-(U1A-PD2{slash}TIM3_ETR{slash}UART5_RX{slash}SDIO_CMD{slash}DCMI_D11{slash}EVENTOUT-Pad83)") (class "Default")
      (node (ref "U1") (pin "83") (pinfunction "PD2/TIM3_ETR/UART5_RX/SDIO_CMD/DCMI_D11/EVENTOUT_83") (pintype "bidirectional"))
    )
    (net (code "74") (name "unconnected-(U1A-PD3{slash}FSMC_CLK{slash}USART2_CTS{slash}EVENTOUT-Pad84)") (class "Default")
      (node (ref "U1") (pin "84") (pinfunction "PD3/FSMC_CLK/USART2_CTS/EVENTOUT_84") (pintype "bidirectional"))
    )
    (net (code "75") (name "unconnected-(U1A-PD4{slash}FSMC_NOE{slash}USART2_RTS{slash}EVENTOUT-Pad85)") (class "Default")
      (node (ref "U1") (pin "85") (pinfunction "PD4/FSMC_NOE/USART2_RTS/EVENTOUT_85") (pintype "bidirectional"))
    )
    (net (code "76") (name "unconnected-(U1A-PD5{slash}FSMC_NWE{slash}USART2_TX{slash}EVENTOUT-Pad86)") (class "Default")
      (node (ref "U1") (pin "86") (pinfunction "PD5/FSMC_NWE/USART2_TX/EVENTOUT_86") (pintype "bidirectional"))
    )
    (net (code "77") (name "unconnected-(U1A-PD6{slash}FSMC_NWAIT{slash}USART2_RX{slash}EVENTOUT-Pad87)") (class "Default")
      (node (ref "U1") (pin "87") (pinfunction "PD6/FSMC_NWAIT/USART2_RX/EVENTOUT_87") (pintype "bidirectional"))
    )
    (net (code "78") (name "unconnected-(U1A-PD8{slash}FSMC_D13{slash}USART3_TX{slash}EVENTOUT-Pad55)") (class "Default")
      (node (ref "U1") (pin "55") (pinfunction "PD8/FSMC_D13/USART3_TX/EVENTOUT_55") (pintype "bidirectional"))
    )
    (net (code "79") (name "unconnected-(U1A-PD9{slash}FSMC_D14{slash}USART3_RX{slash}EVENTOUT-Pad56)") (class "Default")
      (node (ref "U1") (pin "56") (pinfunction "PD9/FSMC_D14/USART3_RX/EVENTOUT_56") (pintype "bidirectional"))
    )
    (net (code "80") (name "unconnected-(U1A-PD10{slash}FSMC_D15{slash}USART3_CK{slash}EVENTOUT-Pad57)") (class "Default")
      (node (ref "U1") (pin "57") (pinfunction "PD10/FSMC_D15/USART3_CK/EVENTOUT_57") (pintype "bidirectional"))
    )
    (net (code "81") (name "unconnected-(U1A-PD11{slash}FSMC_CLE{slash}FSMC_A16{slash}USART3_CTS{slash}EVENTOUT-Pad58)") (class "Default")
      (node (ref "U1") (pin "58") (pinfunction "PD11/FSMC_CLE/FSMC_A16/USART3_CTS/EVENTOUT_58") (pintype "bidirectional"))
    )
    (net (code "82") (name "unconnected-(U1A-PD12{slash}FSMC_ALE{slash}FSMC_A17{slash}TIM4_CH1{slash}USART3_RTS{slash}EVENTOUT-Pad59)") (class "Default")
      (node (ref "U1") (pin "59") (pinfunction "PD12/FSMC_ALE/FSMC_A17/TIM4_CH1/USART3_RTS/EVENTOUT_59") (pintype "bidirectional"))
    )
    (net (code "83") (name "unconnected-(U1A-PD13{slash}FSMC_A18{slash}TIM4_CH2{slash}EVENTOUT-Pad60)") (class "Default")
      (node (ref "U1") (pin "60") (pinfunction "PD13/FSMC_A18/TIM4_CH2/EVENTOUT_60") (pintype "bidirectional"))
    )
    (net (code "84") (name "unconnected-(U1A-PD14{slash}FSMC_D0{slash}TIM4_CH3{slash}EVENTOUT-Pad61)") (class "Default")
      (node (ref "U1") (pin "61") (pinfunction "PD14/FSMC_D0/TIM4_CH3/EVENTOUT_61") (pintype "bidirectional"))
    )
    (net (code "85") (name "unconnected-(U1A-PD15{slash}FSMC_D1{slash}TIM4_CH4{slash}EVENTOUT-Pad62)") (class "Default")
      (node (ref "U1") (pin "62") (pinfunction "PD15/FSMC_D1/TIM4_CH4/EVENTOUT_62") (pintype "bidirectional"))
    )
    (net (code "86") (name "unconnected-(U1A-PE0{slash}TIM4_ETR{slash}FSMC_NBL0{slash}DCMI_D2{slash}EVENTOUT-Pad97)") (class "Default")
      (node (ref "U1") (pin "97") (pinfunction "PE0/TIM4_ETR/FSMC_NBL0/DCMI_D2/EVENTOUT_97") (pintype "bidirectional"))
    )
    (net (code "87") (name "unconnected-(U1A-PE1{slash}FSMC_NBL1{slash}DCMI_D3{slash}EVENTOUT-Pad98)") (class "Default")
      (node (ref "U1") (pin "98") (pinfunction "PE1/FSMC_NBL1/DCMI_D3/EVENTOUT_98") (pintype "bidirectional"))
    )
    (net (code "88") (name "unconnected-(U1A-PE2{slash}TRACECLK{slash}FSMC_A23{slash}ETH_MII_TXD3{slash}EVENTOUT-Pad1)") (class "Default")
      (node (ref "U1") (pin "1") (pinfunction "PE2/TRACECLK/FSMC_A23/ETH_MII_TXD3/EVENTOUT_1") (pintype "bidirectional"))
    )
    (net (code "89") (name "unconnected-(U1A-PE3{slash}TRACED0{slash}FSMC_A19{slash}EVENTOUT-Pad2)") (class "Default")
      (node (ref "U1") (pin "2") (pinfunction "PE3/TRACED0/FSMC_A19/EVENTOUT_2") (pintype "bidirectional"))
    )
    (net (code "90") (name "unconnected-(U1A-PE5{slash}TRACED2{slash}FSMC_A21{slash}TIM9_CH1{slash}DCMI_D6{slash}EVENTOUT-Pad4)") (class "Default")
      (node (ref "U1") (pin "4") (pinfunction "PE5/TRACED2/FSMC_A21/TIM9_CH1/DCMI_D6/EVENTOUT_4") (pintype "bidirectional"))
    )
    (net (code "91") (name "unconnected-(U1A-PE6{slash}TRACED3{slash}FSMC_A22{slash}TIM9_CH2{slash}DCMI_D7{slash}EVENTOUT-Pad5)") (class "Default")
      (node (ref "U1") (pin "5") (pinfunction "PE6/TRACED3/FSMC_A22/TIM9_CH2/DCMI_D7/EVENTOUT_5") (pintype "bidirectional"))
    )
    (net (code "92") (name "unconnected-(U1A-PE7{slash}FSMC_D4{slash}TIM1_ETR{slash}EVENTOUT-Pad38)") (class "Default")
      (node (ref "U1") (pin "38") (pinfunction "PE7/FSMC_D4/TIM1_ETR/EVENTOUT_38") (pintype "bidirectional"))
    )
    (net (code "93") (name "unconnected-(U1A-PE8{slash}FSMC_D5{slash}TIM1_CH1N{slash}EVENTOUT-Pad39)") (class "Default")
      (node (ref "U1") (pin "39") (pinfunction "PE8/FSMC_D5/TIM1_CH1N/EVENTOUT_39") (pintype "bidirectional"))
    )
    (net (code "94") (name "unconnected-(U1A-PE9{slash}FSMC_D6{slash}TIM1_CH1{slash}EVENTOUT-Pad40)") (class "Default")
      (node (ref "U1") (pin "40") (pinfunction "PE9/FSMC_D6/TIM1_CH1/EVENTOUT_40") (pintype "bidirectional"))
    )
    (net (code "95") (name "unconnected-(U1A-PE10{slash}FSMC_D7{slash}TIM1_CH2N{slash}EVENTOUT-Pad41)") (class "Default")
      (node (ref "U1") (pin "41") (pinfunction "PE10/FSMC_D7/TIM1_CH2N/EVENTOUT_41") (pintype "bidirectional"))
    )
    (net (code "96") (name "unconnected-(U1A-PE11{slash}FSMC_D8{slash}TIM1_CH2{slash}EVENTOUT-Pad42)") (class "Default")
      (node (ref "U1") (pin "42") (pinfunction "PE11/FSMC_D8/TIM1_CH2/EVENTOUT_42") (pintype "bidirectional"))
    )
    (net (code "97") (name "unconnected-(U1A-PE12{slash}FSMC_D9{slash}TIM1_CH3N{slash}EVENTOUT-Pad43)") (class "Default")
      (node (ref "U1") (pin "43") (pinfunction "PE12/FSMC_D9/TIM1_CH3N/EVENTOUT_43") (pintype "bidirectional"))
    )
    (net (code "98") (name "unconnected-(U1A-PE13{slash}FSMC_D10{slash}TIM1_CH3{slash}EVENTOUT-Pad44)") (class "Default")
      (node (ref "U1") (pin "44") (pinfunction "PE13/FSMC_D10/TIM1_CH3/EVENTOUT_44") (pintype "bidirectional"))
    )
    (net (code "99") (name "unconnected-(U1A-PE14{slash}FSMC_D11{slash}TIM1_CH4{slash}EVENTOUT-Pad45)") (class "Default")
      (node (ref "U1") (pin "45") (pinfunction "PE14/FSMC_D11/TIM1_CH4/EVENTOUT_45") (pintype "bidirectional"))
    )
    (net (code "100") (name "unconnected-(U1A-PE15{slash}FSMC_D12{slash}TIM1_BKIN{slash}EVENTOUT-Pad46)") (class "Default")
      (node (ref "U1") (pin "46") (pinfunction "PE15/FSMC_D12/TIM1_BKIN/EVENTOUT_46") (pintype "bidirectional"))
    )
    (net (code "101") (name "unconnected-(U1A-PH0-OSC_IN(PH0){slash}EVENTOUT{slash}OSC_IN-Pad12)") (class "Default")
      (node (ref "U1") (pin "12") (pinfunction "PH0-OSC_IN(PH0)/EVENTOUT/OSC_IN_12") (pintype "bidirectional"))
    )
    (net (code "102") (name "unconnected-(U1A-PH1-OSC_OUT(PH1){slash}EVENTOUT{slash}OSC_OUT-Pad13)") (class "Default")
      (node (ref "U1") (pin "13") (pinfunction "PH1-OSC_OUT(PH1)/EVENTOUT/OSC_OUT_13") (pintype "bidirectional"))
    )
  )
)
